# 04_MEMORY.net
KiCad netlist of a schematic drawn in Altium Designer
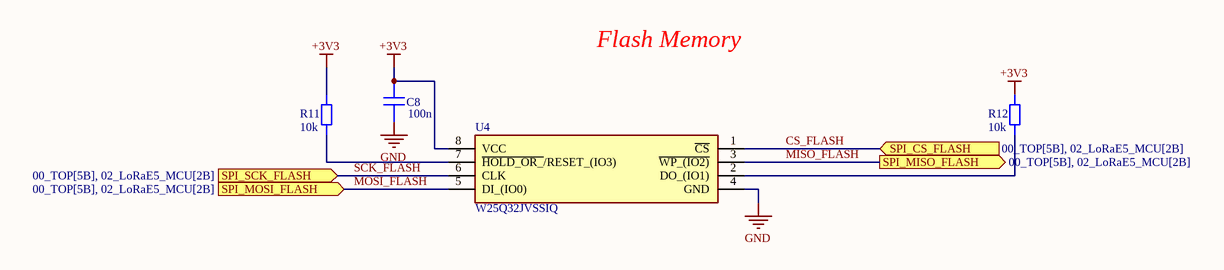
[diagram p0: 04_MEMORY.SchDoc]

(export (version "E")
  (design (tool "Eeschema 10.0.6"))
  (components
    (comp (ref "C8")
      (value "100n")
      (footprint "Capacitor_SMD:0603_1608m")
      (libsource (lib "TrashTrack_SCH_LIB") (part "Generic_Capacitor"))
    )
    (comp (ref "R11")
      (value "10k")
      (footprint "Resistor_SMD:0603_1608m")
      (libsource (lib "TrashTrack_SCH_LIB") (part "Generic Resistor"))
    )
    (comp (ref "R12")
      (value "10k")
      (footprint "Resistor_SMD:0603_1608m")
      (libsource (lib "TrashTrack_SCH_LIB") (part "Generic Resistor"))
    )
    (comp (ref "U4")
      (value "W25Q32JVSSIQ")
      (footprint "W25Q32JVSSIQ")
      (fields (field (name "MOUSER PART NUMBER") "454-W25Q32JVSSIQ"))
      (libsource (lib "TrashTrack_SCH_LIB") (part "W25Q32JVSSIQ"))
    )
  )
  (nets
    (net (code "1") (name "+3V3") (class "Default")
      (node (ref "C8") (pin "1") (pintype "passive"))
      (node (ref "R11") (pin "1") (pintype "passive"))
      (node (ref "R12") (pin "1") (pintype "passive"))
      (node (ref "U4") (pin "8") (pinfunction "VCC_8") (pintype "passive"))
    )
    (net (code "2") (name "/CS_FLASH") (class "Default")
      (node (ref "U4") (pin "1") (pinfunction "~{CS}_1") (pintype "passive"))
    )
    (net (code "3") (name "/MISO_FLASH") (class "Default")
      (node (ref "U4") (pin "3") (pinfunction "~{WP_(IO2)}_3") (pintype "passive"))
    )
    (net (code "4") (name "/MOSI_FLASH") (class "Default")
      (node (ref "U4") (pin "5") (pinfunction "DI_(IO0)_5") (pintype "passive"))
    )
    (net (code "5") (name "/SCK_FLASH") (class "Default")
      (node (ref "U4") (pin "6") (pinfunction "CLK_6") (pintype "passive"))
    )
    (net (code "6") (name "GND") (class "Default")
      (node (ref "C8") (pin "2") (pintype "passive"))
      (node (ref "U4") (pin "4") (pinfunction "GND_4") (pintype "passive"))
    )
    (net (code "7") (name "Net-(U4-DO_(IO1))") (class "Default")
      (node (ref "R12") (pin "2") (pintype "passive"))
      (node (ref "U4") (pin "2") (pinfunction "DO_(IO1)_2") (pintype "passive"))
    )
    (net (code "8") (name "Net-(U4-~{HOLD_OR_}{slash}RESET_(IO3))") (class "Default")
      (node (ref "R11") (pin "2") (pintype "passive"))
      (node (ref "U4") (pin "7") (pinfunction "~{HOLD_OR_}/RESET_(IO3)_7") (pintype "passive"))
    )
  )
)
